# selector.net
KiCad netlist of a schematic drawn in Altium Designer
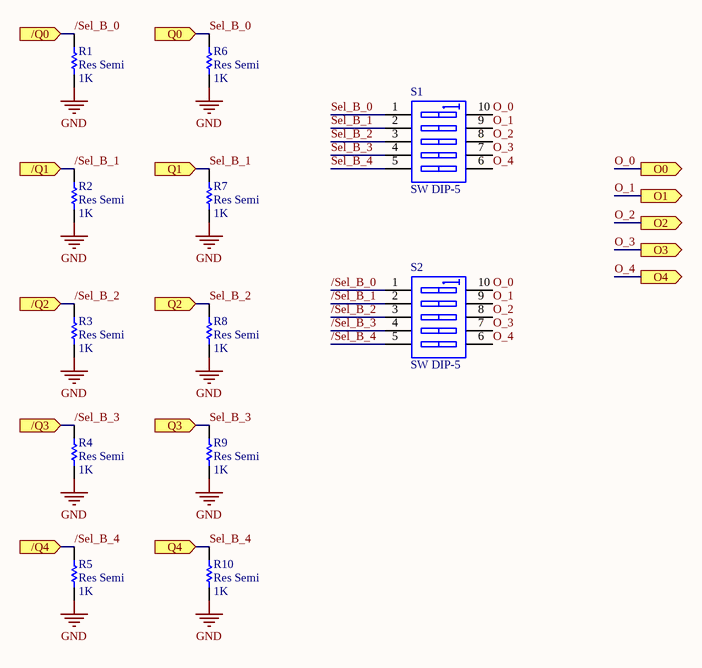
[diagram p0: selector.SchDoc]

(export (version "E")
  (design (tool "Eeschema 10.0.6"))
  (components
    (comp (ref "R1")
      (value "Res Semi")
      (footprint "2012[0805]")
      (description "Semiconductor Resistor")
      (fields (field (name "ALTIUM_VALUE") "1K") (field (name "PUBLISHER") "Altium Limited"))
      (libsource (lib "Miscellaneous Devices") (part "Res Semi"))
    )
    (comp (ref "R2")
      (value "Res Semi")
      (footprint "2012[0805]")
      (description "Semiconductor Resistor")
      (fields (field (name "ALTIUM_VALUE") "1K") (field (name "PUBLISHER") "Altium Limited"))
      (libsource (lib "Miscellaneous Devices") (part "Res Semi"))
    )
    (comp (ref "R3")
      (value "Res Semi")
      (footprint "2012[0805]")
      (description "Semiconductor Resistor")
      (fields (field (name "ALTIUM_VALUE") "1K") (field (name "PUBLISHER") "Altium Limited"))
      (libsource (lib "Miscellaneous Devices") (part "Res Semi"))
    )
    (comp (ref "R4")
      (value "Res Semi")
      (footprint "2012[0805]")
      (description "Semiconductor Resistor")
      (fields (field (name "ALTIUM_VALUE") "1K") (field (name "PUBLISHER") "Altium Limited"))
      (libsource (lib "Miscellaneous Devices") (part "Res Semi"))
    )
    (comp (ref "R5")
      (value "Res Semi")
      (footprint "2012[0805]")
      (description "Semiconductor Resistor")
      (fields (field (name "ALTIUM_VALUE") "1K") (field (name "PUBLISHER") "Altium Limited"))
      (libsource (lib "Miscellaneous Devices") (part "Res Semi"))
    )
    (comp (ref "R6")
      (value "Res Semi")
      (footprint "2012[0805]")
      (description "Semiconductor Resistor")
      (fields (field (name "ALTIUM_VALUE") "1K") (field (name "PUBLISHER") "Altium Limited"))
      (libsource (lib "Miscellaneous Devices") (part "Res Semi"))
    )
    (comp (ref "R7")
      (value "Res Semi")
      (footprint "2012[0805]")
      (description "Semiconductor Resistor")
      (fields (field (name "ALTIUM_VALUE") "1K") (field (name "PUBLISHER") "Altium Limited"))
      (libsource (lib "Miscellaneous Devices") (part "Res Semi"))
    )
    (comp (ref "R8")
      (value "Res Semi")
      (footprint "2012[0805]")
      (description "Semiconductor Resistor")
      (fields (field (name "ALTIUM_VALUE") "1K") (field (name "PUBLISHER") "Altium Limited"))
      (libsource (lib "Miscellaneous Devices") (part "Res Semi"))
    )
    (comp (ref "R9")
      (value "Res Semi")
      (footprint "2012[0805]")
      (description "Semiconductor Resistor")
      (fields (field (name "ALTIUM_VALUE") "1K") (field (name "PUBLISHER") "Altium Limited"))
      (libsource (lib "Miscellaneous Devices") (part "Res Semi"))
    )
    (comp (ref "R10")
      (value "Res Semi")
      (footprint "2012[0805]")
      (description "Semiconductor Resistor")
      (fields (field (name "ALTIUM_VALUE") "1K") (field (name "PUBLISHER") "Altium Limited"))
      (libsource (lib "Miscellaneous Devices") (part "Res Semi"))
    )
    (comp (ref "S1")
      (value "SW DIP-5")
      (footprint "N10A")
      (description "DIP Switch, 5 Position, SPST")
      (fields (field (name "PUBLISHER") "Altium Limited"))
      (libsource (lib "Miscellaneous Devices") (part "SW DIP-5"))
    )
    (comp (ref "S2")
      (value "SW DIP-5")
      (footprint "N10A")
      (description "DIP Switch, 5 Position, SPST")
      (fields (field (name "PUBLISHER") "Altium Limited"))
      (libsource (lib "Miscellaneous Devices") (part "SW DIP-5"))
    )
  )
  (nets
    (net (code "1") (name "/O_0") (class "Default")
      (node (ref "S1") (pin "10") (pinfunction "B1_10") (pintype "passive"))
      (node (ref "S2") (pin "10") (pinfunction "B1_10") (pintype "passive"))
    )
    (net (code "2") (name "/O_1") (class "Default")
      (node (ref "S1") (pin "9") (pinfunction "B2_9") (pintype "passive"))
      (node (ref "S2") (pin "9") (pinfunction "B2_9") (pintype "passive"))
    )
    (net (code "3") (name "/O_2") (class "Default")
      (node (ref "S1") (pin "8") (pinfunction "B3_8") (pintype "passive"))
      (node (ref "S2") (pin "8") (pinfunction "B3_8") (pintype "passive"))
    )
    (net (code "4") (name "/O_3") (class "Default")
      (node (ref "S1") (pin "7") (pinfunction "B4_7") (pintype "passive"))
      (node (ref "S2") (pin "7") (pinfunction "B4_7") (pintype "passive"))
    )
    (net (code "5") (name "/O_4") (class "Default")
      (node (ref "S1") (pin "6") (pinfunction "B5_6") (pintype "passive"))
      (node (ref "S2") (pin "6") (pinfunction "B5_6") (pintype "passive"))
    )
    (net (code "6") (name "/Sel_B_0") (class "Default")
      (node (ref "R6") (pin "2") (pinfunction "2_2") (pintype "passive"))
      (node (ref "S1") (pin "1") (pinfunction "A1_1") (pintype "passive"))
    )
    (net (code "7") (name "/Sel_B_1") (class "Default")
      (node (ref "R7") (pin "2") (pinfunction "2_2") (pintype "passive"))
      (node (ref "S1") (pin "2") (pinfunction "A2_2") (pintype "passive"))
    )
    (net (code "8") (name "/Sel_B_2") (class "Default")
      (node (ref "R8") (pin "2") (pinfunction "2_2") (pintype "passive"))
      (node (ref "S1") (pin "3") (pinfunction "A3_3") (pintype "passive"))
    )
    (net (code "9") (name "/Sel_B_3") (class "Default")
      (node (ref "R9") (pin "2") (pinfunction "2_2") (pintype "passive"))
      (node (ref "S1") (pin "4") (pinfunction "A4_4") (pintype "passive"))
    )
    (net (code "10") (name "/Sel_B_4") (class "Default")
      (node (ref "R10") (pin "2") (pinfunction "2_2") (pintype "passive"))
      (node (ref "S1") (pin "5") (pinfunction "A5_5") (pintype "passive"))
    )
    (net (code "11") (name "/{slash}Sel_B_0") (class "Default")
      (node (ref "R1") (pin "2") (pinfunction "2_2") (pintype "passive"))
      (node (ref "S2") (pin "1") (pinfunction "A1_1") (pintype "passive"))
    )
    (net (code "12") (name "/{slash}Sel_B_1") (class "Default")
      (node (ref "R2") (pin "2") (pinfunction "2_2") (pintype "passive"))
      (node (ref "S2") (pin "2") (pinfunction "A2_2") (pintype "passive"))
    )
    (net (code "13") (name "/{slash}Sel_B_2") (class "Default")
      (node (ref "R3") (pin "2") (pinfunction "2_2") (pintype "passive"))
      (node (ref "S2") (pin "3") (pinfunction "A3_3") (pintype "passive"))
    )
    (net (code "14") (name "/{slash}Sel_B_3") (class "Default")
      (node (ref "R4") (pin "2") (pinfunction "2_2") (pintype "passive"))
      (node (ref "S2") (pin "4") (pinfunction "A4_4") (pintype "passive"))
    )
    (net (code "15") (name "/{slash}Sel_B_4") (class "Default")
      (node (ref "R5") (pin "2") (pinfunction "2_2") (pintype "passive"))
      (node (ref "S2") (pin "5") (pinfunction "A5_5") (pintype "passive"))
    )
    (net (code "16") (name "GND") (class "Default")
      (node (ref "R1") (pin "1") (pinfunction "1_1") (pintype "passive"))
      (node (ref "R10") (pin "1") (pinfunction "1_1") (pintype "passive"))
      (node (ref "R2") (pin "1") (pinfunction "1_1") (pintype "passive"))
      (node (ref "R3") (pin "1") (pinfunction "1_1") (pintype "passive"))
      (node (ref "R4") (pin "1") (pinfunction "1_1") (pintype "passive"))
      (node (ref "R5") (pin "1") (pinfunction "1_1") (pintype "passive"))
      (node (ref "R6") (pin "1") (pinfunction "1_1") (pintype "passive"))
      (node (ref "R7") (pin "1") (pinfunction "1_1") (pintype "passive"))
      (node (ref "R8") (pin "1") (pinfunction "1_1") (pintype "passive"))
      (node (ref "R9") (pin "1") (pinfunction "1_1") (pintype "passive"))
    )
  )
)
